# Programmer.net
KiCad netlist of a schematic drawn in EAGLE
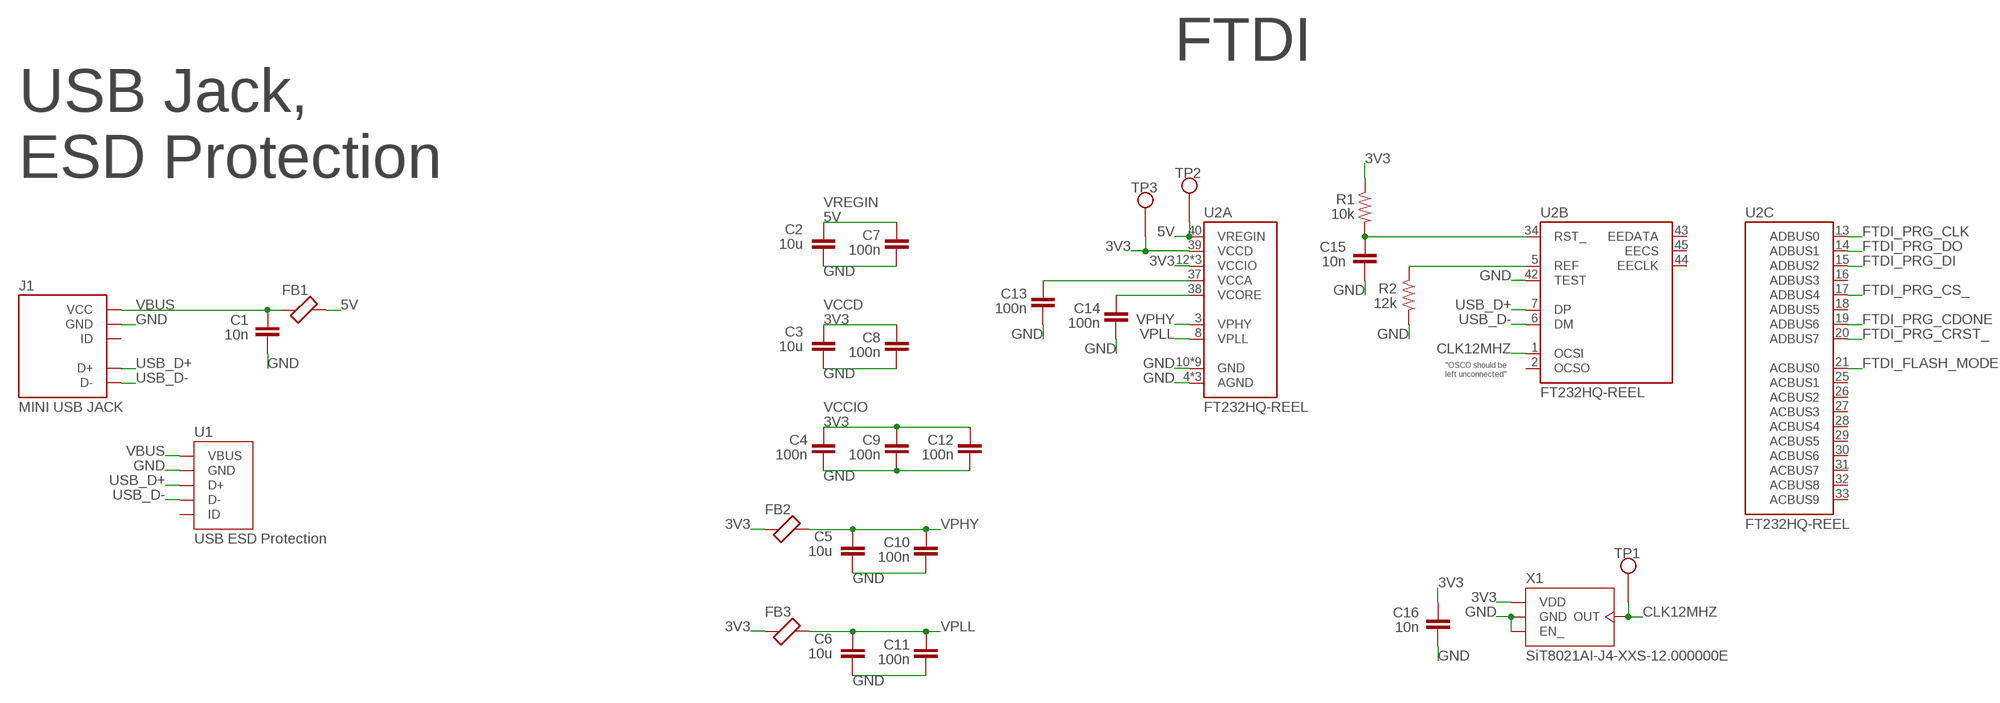
[diagram p0: schematic, sheet 1, part 1 of 2]
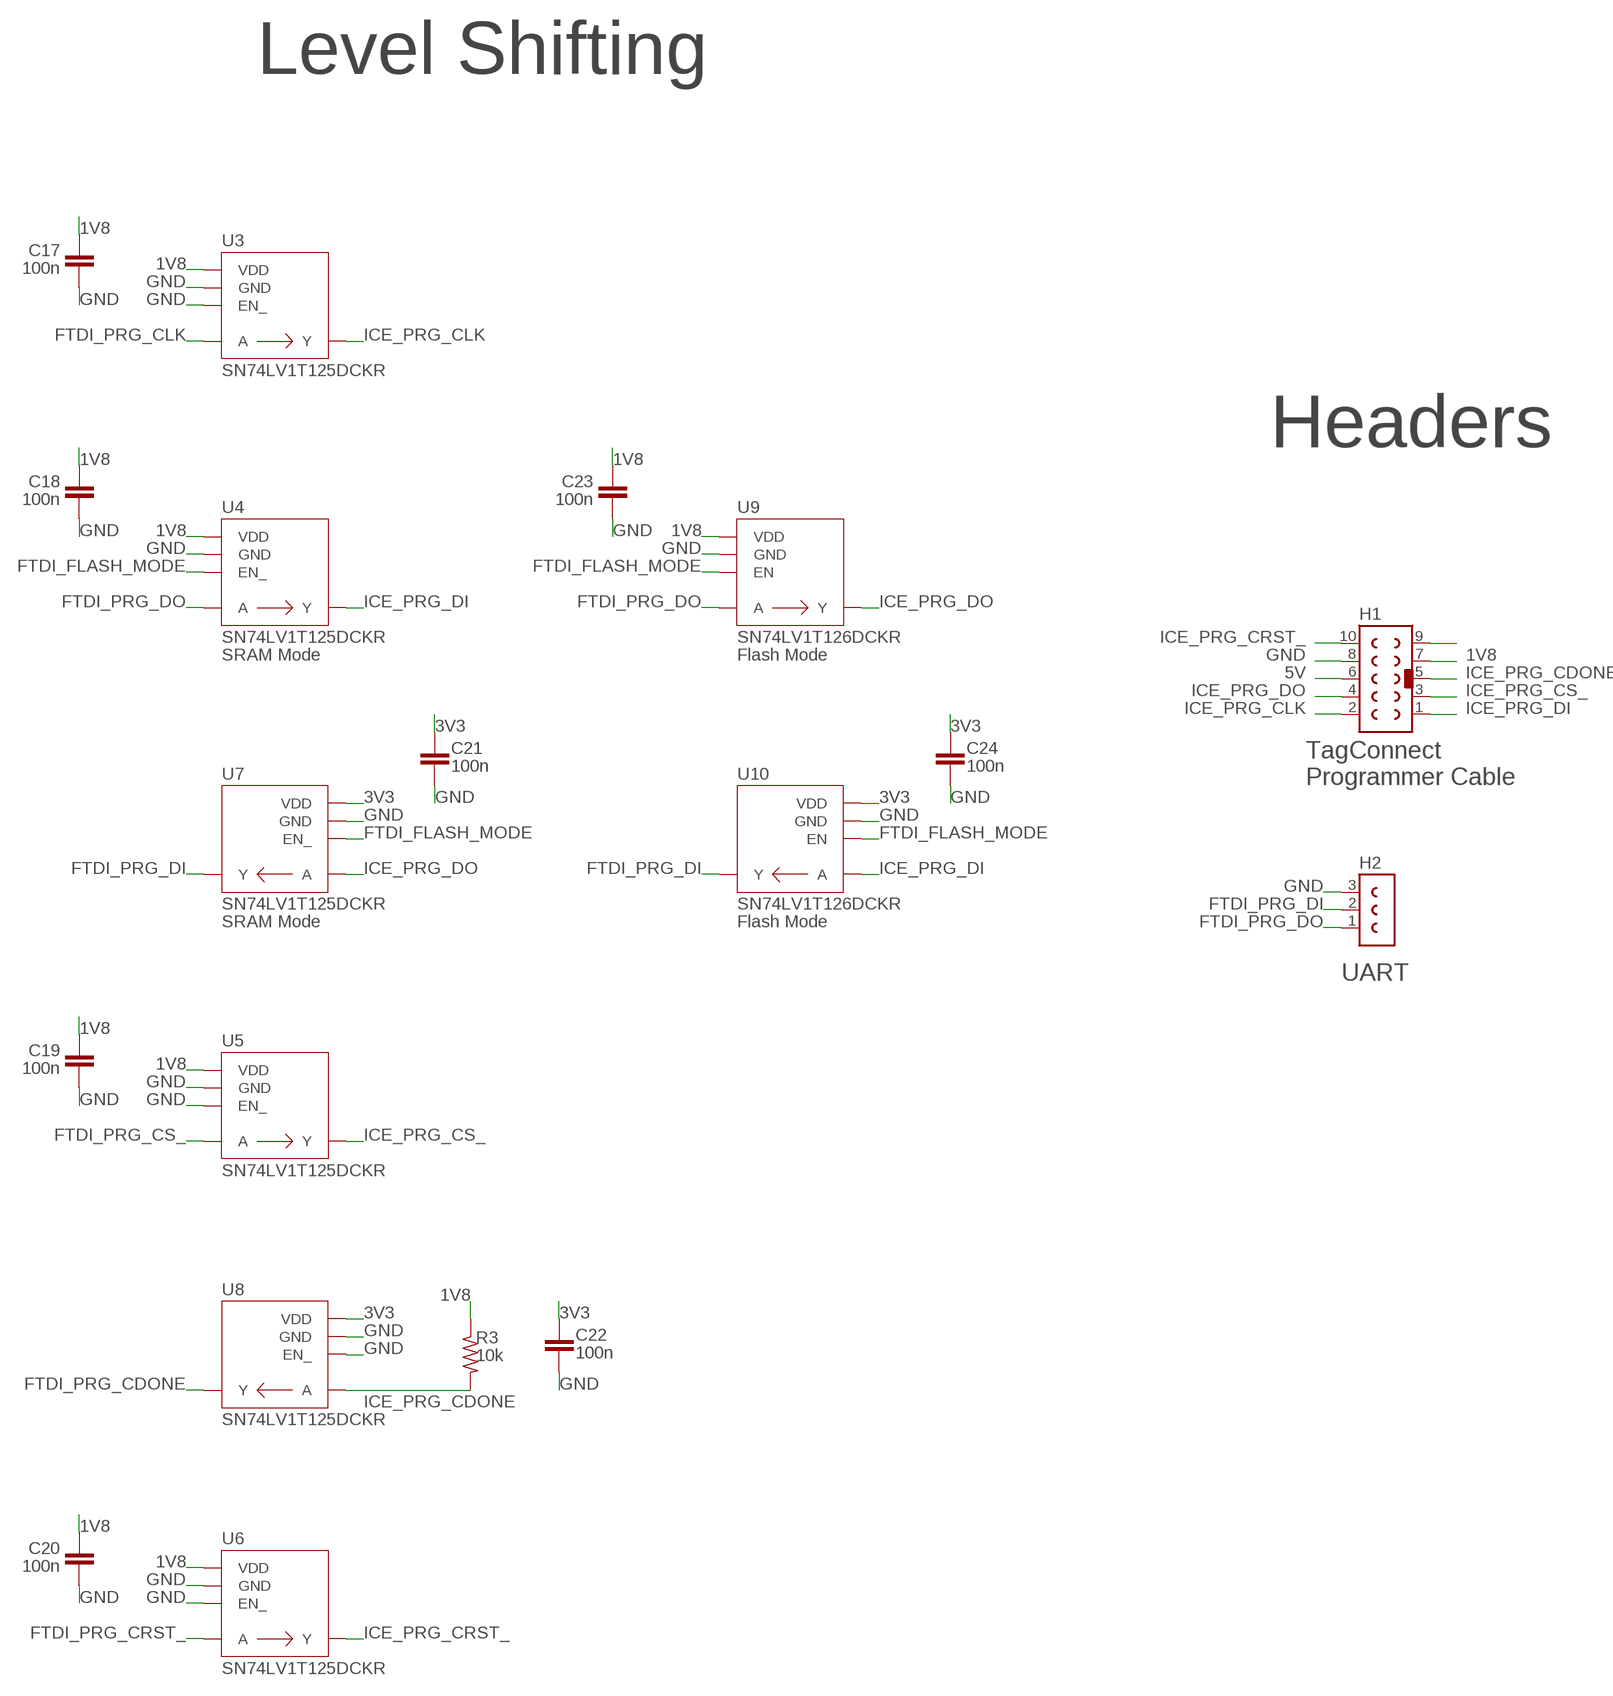
[diagram p1: schematic, sheet 1, part 2 of 2]

(export (version "E")
  (design (tool "Eeschema 10.0.6"))
  (components
    (comp (ref "C1")
      (value "10n")
      (footprint "eagle-import:0402")
      (fields (field (name "MFG") "Murata"))
      (libsource (lib "eagle-import") (part "CAPACITOR0402"))
    )
    (comp (ref "C2")
      (value "10u")
      (footprint "eagle-import:1206")
      (fields (field (name "MFG") "Murata"))
      (libsource (lib "eagle-import") (part "CAPACITOR1206"))
    )
    (comp (ref "C3")
      (value "10u")
      (footprint "eagle-import:1206")
      (fields (field (name "MFG") "Murata"))
      (libsource (lib "eagle-import") (part "CAPACITOR1206"))
    )
    (comp (ref "C4")
      (value "100n")
      (footprint "eagle-import:0402")
      (fields (field (name "MFG") "Murata"))
      (libsource (lib "eagle-import") (part "CAPACITOR0402"))
    )
    (comp (ref "C5")
      (value "10u")
      (footprint "eagle-import:1206")
      (fields (field (name "MFG") "Murata"))
      (libsource (lib "eagle-import") (part "CAPACITOR1206"))
    )
    (comp (ref "C6")
      (value "10u")
      (footprint "eagle-import:1206")
      (fields (field (name "MFG") "Murata"))
      (libsource (lib "eagle-import") (part "CAPACITOR1206"))
    )
    (comp (ref "C7")
      (value "100n")
      (footprint "eagle-import:0402")
      (fields (field (name "MFG") "Murata"))
      (libsource (lib "eagle-import") (part "CAPACITOR0402"))
    )
    (comp (ref "C8")
      (value "100n")
      (footprint "eagle-import:0402")
      (fields (field (name "MFG") "Murata"))
      (libsource (lib "eagle-import") (part "CAPACITOR0402"))
    )
    (comp (ref "C9")
      (value "100n")
      (footprint "eagle-import:0402")
      (fields (field (name "MFG") "Murata"))
      (libsource (lib "eagle-import") (part "CAPACITOR0402"))
    )
    (comp (ref "C10")
      (value "100n")
      (footprint "eagle-import:0402")
      (fields (field (name "MFG") "Murata"))
      (libsource (lib "eagle-import") (part "CAPACITOR0402"))
    )
    (comp (ref "C11")
      (value "100n")
      (footprint "eagle-import:0402")
      (fields (field (name "MFG") "Murata"))
      (libsource (lib "eagle-import") (part "CAPACITOR0402"))
    )
    (comp (ref "C12")
      (value "100n")
      (footprint "eagle-import:0402")
      (fields (field (name "MFG") "Murata"))
      (libsource (lib "eagle-import") (part "CAPACITOR0402"))
    )
    (comp (ref "C13")
      (value "100n")
      (footprint "eagle-import:0402")
      (fields (field (name "MFG") "Murata"))
      (libsource (lib "eagle-import") (part "CAPACITOR0402"))
    )
    (comp (ref "C14")
      (value "100n")
      (footprint "eagle-import:0402")
      (fields (field (name "MFG") "Murata"))
      (libsource (lib "eagle-import") (part "CAPACITOR0402"))
    )
    (comp (ref "C15")
      (value "10n")
      (footprint "eagle-import:0402")
      (fields (field (name "MFG") "Murata"))
      (libsource (lib "eagle-import") (part "CAPACITOR0402"))
    )
    (comp (ref "C16")
      (value "10n")
      (footprint "eagle-import:0402")
      (fields (field (name "MFG") "Murata"))
      (libsource (lib "eagle-import") (part "CAPACITOR0402"))
    )
    (comp (ref "C17")
      (value "100n")
      (footprint "eagle-import:0402")
      (fields (field (name "MFG") "Murata"))
      (libsource (lib "eagle-import") (part "CAPACITOR0402"))
    )
    (comp (ref "C18")
      (value "100n")
      (footprint "eagle-import:0402")
      (fields (field (name "MFG") "Murata"))
      (libsource (lib "eagle-import") (part "CAPACITOR0402"))
    )
    (comp (ref "C19")
      (value "100n")
      (footprint "eagle-import:0402")
      (fields (field (name "MFG") "Murata"))
      (libsource (lib "eagle-import") (part "CAPACITOR0402"))
    )
    (comp (ref "C20")
      (value "100n")
      (footprint "eagle-import:0402")
      (fields (field (name "MFG") "Murata"))
      (libsource (lib "eagle-import") (part "CAPACITOR0402"))
    )
    (comp (ref "C21")
      (value "100n")
      (footprint "eagle-import:0402")
      (fields (field (name "MFG") "Murata"))
      (libsource (lib "eagle-import") (part "CAPACITOR0402"))
    )
    (comp (ref "C22")
      (value "100n")
      (footprint "eagle-import:0402")
      (fields (field (name "MFG") "Murata"))
      (libsource (lib "eagle-import") (part "CAPACITOR0402"))
    )
    (comp (ref "C23")
      (value "100n")
      (footprint "eagle-import:0402")
      (fields (field (name "MFG") "Murata"))
      (libsource (lib "eagle-import") (part "CAPACITOR0402"))
    )
    (comp (ref "C24")
      (value "100n")
      (footprint "eagle-import:0402")
      (fields (field (name "MFG") "Murata"))
      (libsource (lib "eagle-import") (part "CAPACITOR0402"))
    )
    (comp (ref "FB1")
      (value "FERRITE-BEAD1206")
      (footprint "eagle-import:1206")
      (fields (field (name "MFG") "Murata"))
      (libsource (lib "eagle-import") (part "FERRITE-BEAD1206"))
    )
    (comp (ref "FB2")
      (value "FERRITE-BEAD1206")
      (footprint "eagle-import:1206")
      (fields (field (name "MFG") "Murata"))
      (libsource (lib "eagle-import") (part "FERRITE-BEAD1206"))
    )
    (comp (ref "FB3")
      (value "FERRITE-BEAD1206")
      (footprint "eagle-import:1206")
      (fields (field (name "MFG") "Murata"))
      (libsource (lib "eagle-import") (part "FERRITE-BEAD1206"))
    )
    (comp (ref "H1")
      (value "WURTH-61201021621")
      (footprint "eagle-import:WURTH-61201021621")
      (fields (field (name "MFG") "Wurth Elektronik"))
      (libsource (lib "eagle-import") (part "WURTH-61201021621"))
    )
    (comp (ref "H2")
      (value "HEADER-1X3")
      (footprint "eagle-import:HEADER-1X3")
      (fields (field (name "MFG") "Molex"))
      (libsource (lib "eagle-import") (part "HEADER-1X3"))
    )
    (comp (ref "J1")
      (value "MINI-USB-JACK")
      (footprint "eagle-import:AMPHENOLFCI-10033526-N3222MLF")
      (fields (field (name "MFG") "Amphenol FCI"))
      (libsource (lib "eagle-import") (part "MINI-USB-JACK"))
    )
    (comp (ref "R1")
      (value "10k")
      (footprint "eagle-import:0402")
      (fields (field (name "MFG") "Vishay"))
      (libsource (lib "eagle-import") (part "RESISTOR0402"))
    )
    (comp (ref "R2")
      (value "12k")
      (footprint "eagle-import:0402")
      (fields (field (name "MFG") "Vishay"))
      (libsource (lib "eagle-import") (part "RESISTOR0402"))
    )
    (comp (ref "R3")
      (value "10k")
      (footprint "eagle-import:0402")
      (fields (field (name "MFG") "Vishay"))
      (libsource (lib "eagle-import") (part "RESISTOR0402"))
    )
    (comp (ref "TP1")
      (value "TEST-POINT")
      (footprint "eagle-import:TEST-POINT")
      (libsource (lib "eagle-import") (part "TEST-POINT"))
    )
    (comp (ref "TP2")
      (value "TEST-POINT")
      (footprint "eagle-import:TEST-POINT")
      (libsource (lib "eagle-import") (part "TEST-POINT"))
    )
    (comp (ref "TP3")
      (value "TEST-POINT")
      (footprint "eagle-import:TEST-POINT")
      (libsource (lib "eagle-import") (part "TEST-POINT"))
    )
    (comp (ref "U1")
      (value "TPD4S012DRYR")
      (footprint "eagle-import:TPD4S012DRYR")
      (fields (field (name "MFG") "Texas Instruments"))
      (libsource (lib "eagle-import") (part "TPD4S012DRYR"))
    )
    (comp (ref "U2")
      (value "FT232HQ")
      (footprint "eagle-import:FT232HQ")
      (fields (field (name "MFG") "FTDI") (field (name "PN") "FT232HQ-REEL"))
      (libsource (lib "eagle-import") (part "FT232HQ"))
    )
    (comp (ref "U3")
      (value "SN74LV1T125DCKR")
      (footprint "eagle-import:SN74LV1T12XDCKR")
      (fields (field (name "PN") "SN74LV1T125DCKR") (field (name "MFG") "Texas Instruments"))
      (libsource (lib "eagle-import") (part "SN74LV1T125DCKR"))
    )
    (comp (ref "U4")
      (value "SN74LV1T125DCKR")
      (footprint "eagle-import:SN74LV1T12XDCKR")
      (fields (field (name "PN") "SN74LV1T125DCKR") (field (name "MFG") "Texas Instruments"))
      (libsource (lib "eagle-import") (part "SN74LV1T125DCKR"))
    )
    (comp (ref "U5")
      (value "SN74LV1T125DCKR")
      (footprint "eagle-import:SN74LV1T12XDCKR")
      (fields (field (name "PN") "SN74LV1T125DCKR") (field (name "MFG") "Texas Instruments"))
      (libsource (lib "eagle-import") (part "SN74LV1T125DCKR"))
    )
    (comp (ref "U6")
      (value "SN74LV1T125DCKR")
      (footprint "eagle-import:SN74LV1T12XDCKR")
      (fields (field (name "PN") "SN74LV1T125DCKR") (field (name "MFG") "Texas Instruments"))
      (libsource (lib "eagle-import") (part "SN74LV1T125DCKR"))
    )
    (comp (ref "U7")
      (value "SN74LV1T125DCKR")
      (footprint "eagle-import:SN74LV1T12XDCKR")
      (fields (field (name "PN") "SN74LV1T125DCKR") (field (name "MFG") "Texas Instruments"))
      (libsource (lib "eagle-import") (part "SN74LV1T125DCKR"))
    )
    (comp (ref "U8")
      (value "SN74LV1T125DCKR")
      (footprint "eagle-import:SN74LV1T12XDCKR")
      (fields (field (name "PN") "SN74LV1T125DCKR") (field (name "MFG") "Texas Instruments"))
      (libsource (lib "eagle-import") (part "SN74LV1T125DCKR"))
    )
    (comp (ref "U9")
      (value "SN74LV1T126DCKR")
      (footprint "eagle-import:SN74LV1T12XDCKR")
      (fields (field (name "PN") "SN74LV1T126DCKR") (field (name "MFG") "Texas Instruments"))
      (libsource (lib "eagle-import") (part "SN74LV1T126DCKR"))
    )
    (comp (ref "U10")
      (value "SN74LV1T126DCKR")
      (footprint "eagle-import:SN74LV1T12XDCKR")
      (fields (field (name "PN") "SN74LV1T126DCKR") (field (name "MFG") "Texas Instruments"))
      (libsource (lib "eagle-import") (part "SN74LV1T126DCKR"))
    )
    (comp (ref "X1")
      (value "SITIME-SIT8021")
      (footprint "eagle-import:SITIME-SIT8021")
      (fields (field (name "MFG") "SiTime") (field (name "PN") "SiT8021AI-J4-XXS-12.000000E"))
      (libsource (lib "eagle-import") (part "SITIME-SIT8021"))
    )
  )
  (nets
    (net (code "1") (name "/1V8") (class "Default")
      (node (ref "C17") (pin "1") (pinfunction "1_1") (pintype "bidirectional"))
      (node (ref "C18") (pin "1") (pinfunction "1_1") (pintype "bidirectional"))
      (node (ref "C19") (pin "1") (pinfunction "1_1") (pintype "bidirectional"))
      (node (ref "C20") (pin "1") (pinfunction "1_1") (pintype "bidirectional"))
      (node (ref "C23") (pin "1") (pinfunction "1_1") (pintype "bidirectional"))
      (node (ref "H1") (pin "7") (pinfunction "7_7") (pintype "bidirectional"))
      (node (ref "R3") (pin "1") (pinfunction "1_1") (pintype "bidirectional"))
      (node (ref "U3") (pin "5") (pinfunction "VDD_5") (pintype "bidirectional"))
      (node (ref "U4") (pin "5") (pinfunction "VDD_5") (pintype "bidirectional"))
      (node (ref "U5") (pin "5") (pinfunction "VDD_5") (pintype "bidirectional"))
      (node (ref "U6") (pin "5") (pinfunction "VDD_5") (pintype "bidirectional"))
      (node (ref "U9") (pin "5") (pinfunction "VDD_5") (pintype "bidirectional"))
    )
    (net (code "2") (name "/3V3") (class "Default")
      (node (ref "C12") (pin "1") (pinfunction "1_1") (pintype "bidirectional"))
      (node (ref "C16") (pin "1") (pinfunction "1_1") (pintype "bidirectional"))
      (node (ref "C21") (pin "1") (pinfunction "1_1") (pintype "bidirectional"))
      (node (ref "C22") (pin "1") (pinfunction "1_1") (pintype "bidirectional"))
      (node (ref "C24") (pin "1") (pinfunction "1_1") (pintype "bidirectional"))
      (node (ref "C3") (pin "1") (pinfunction "1_1") (pintype "bidirectional"))
      (node (ref "C4") (pin "1") (pinfunction "1_1") (pintype "bidirectional"))
      (node (ref "C8") (pin "1") (pinfunction "1_1") (pintype "bidirectional"))
      (node (ref "C9") (pin "1") (pinfunction "1_1") (pintype "bidirectional"))
      (node (ref "FB2") (pin "1") (pinfunction "P$1_1") (pintype "bidirectional"))
      (node (ref "FB3") (pin "1") (pinfunction "P$1_1") (pintype "bidirectional"))
      (node (ref "R1") (pin "1") (pinfunction "1_1") (pintype "bidirectional"))
      (node (ref "TP3") (pin "X") (pinfunction "X_X") (pintype "bidirectional"))
      (node (ref "U10") (pin "5") (pinfunction "VDD_5") (pintype "bidirectional"))
      (node (ref "U2") (pin "12") (pinfunction "VCCIO_12") (pintype "bidirectional"))
      (node (ref "U2") (pin "24") (pinfunction "VCCIO_24") (pintype "bidirectional"))
      (node (ref "U2") (pin "39") (pinfunction "VCCD_39") (pintype "bidirectional"))
      (node (ref "U2") (pin "46") (pinfunction "VCCIO_46") (pintype "bidirectional"))
      (node (ref "U7") (pin "5") (pinfunction "VDD_5") (pintype "bidirectional"))
      (node (ref "U8") (pin "5") (pinfunction "VDD_5") (pintype "bidirectional"))
      (node (ref "X1") (pin "3") (pinfunction "VDD_3") (pintype "bidirectional"))
    )
    (net (code "3") (name "/5V") (class "Default")
      (node (ref "C2") (pin "1") (pinfunction "1_1") (pintype "bidirectional"))
      (node (ref "C7") (pin "1") (pinfunction "1_1") (pintype "bidirectional"))
      (node (ref "FB1") (pin "2") (pinfunction "P$2_2") (pintype "bidirectional"))
      (node (ref "H1") (pin "6") (pinfunction "6_6") (pintype "bidirectional"))
      (node (ref "TP2") (pin "X") (pinfunction "X_X") (pintype "bidirectional"))
      (node (ref "U2") (pin "40") (pinfunction "VREGIN_40") (pintype "bidirectional"))
    )
    (net (code "4") (name "/CLK12MHZ") (class "Default")
      (node (ref "TP1") (pin "X") (pinfunction "X_X") (pintype "bidirectional"))
      (node (ref "U2") (pin "1") (pinfunction "OCSI_1") (pintype "bidirectional"))
      (node (ref "X1") (pin "2") (pinfunction "OUT_2") (pintype "bidirectional"))
    )
    (net (code "5") (name "/FTDI_FLASH_MODE") (class "Default")
      (node (ref "U10") (pin "1") (pinfunction "EN_1") (pintype "input"))
      (node (ref "U2") (pin "21") (pinfunction "ACBUS0_21") (pintype "bidirectional"))
      (node (ref "U4") (pin "1") (pinfunction "EN__1") (pintype "input"))
      (node (ref "U7") (pin "1") (pinfunction "EN__1") (pintype "input"))
      (node (ref "U9") (pin "1") (pinfunction "EN_1") (pintype "input"))
    )
    (net (code "6") (name "/FTDI_PRG_CDONE") (class "Default")
      (node (ref "U2") (pin "19") (pinfunction "ADBUS6_19") (pintype "bidirectional"))
      (node (ref "U8") (pin "4") (pinfunction "Y_4") (pintype "input"))
    )
    (net (code "7") (name "/FTDI_PRG_CLK") (class "Default")
      (node (ref "U2") (pin "13") (pinfunction "ADBUS0_13") (pintype "bidirectional"))
      (node (ref "U3") (pin "2") (pinfunction "A_2") (pintype "input"))
    )
    (net (code "8") (name "/FTDI_PRG_CRST_") (class "Default")
      (node (ref "U2") (pin "20") (pinfunction "ADBUS7_20") (pintype "bidirectional"))
      (node (ref "U6") (pin "2") (pinfunction "A_2") (pintype "input"))
    )
    (net (code "9") (name "/FTDI_PRG_CS_") (class "Default")
      (node (ref "U2") (pin "17") (pinfunction "ADBUS4_17") (pintype "bidirectional"))
      (node (ref "U5") (pin "2") (pinfunction "A_2") (pintype "input"))
    )
    (net (code "10") (name "/FTDI_PRG_DI") (class "Default")
      (node (ref "H2") (pin "2") (pinfunction "2_2") (pintype "bidirectional"))
      (node (ref "U10") (pin "4") (pinfunction "Y_4") (pintype "input"))
      (node (ref "U2") (pin "15") (pinfunction "ADBUS2_15") (pintype "bidirectional"))
      (node (ref "U7") (pin "4") (pinfunction "Y_4") (pintype "input"))
    )
    (net (code "11") (name "/FTDI_PRG_DO") (class "Default")
      (node (ref "H2") (pin "1") (pinfunction "1_1") (pintype "bidirectional"))
      (node (ref "U2") (pin "14") (pinfunction "ADBUS1_14") (pintype "bidirectional"))
      (node (ref "U4") (pin "2") (pinfunction "A_2") (pintype "input"))
      (node (ref "U9") (pin "2") (pinfunction "A_2") (pintype "input"))
    )
    (net (code "12") (name "/GND") (class "Default")
      (node (ref "C1") (pin "2") (pinfunction "2_2") (pintype "bidirectional"))
      (node (ref "C10") (pin "2") (pinfunction "2_2") (pintype "bidirectional"))
      (node (ref "C11") (pin "2") (pinfunction "2_2") (pintype "bidirectional"))
      (node (ref "C12") (pin "2") (pinfunction "2_2") (pintype "bidirectional"))
      (node (ref "C13") (pin "2") (pinfunction "2_2") (pintype "bidirectional"))
      (node (ref "C14") (pin "2") (pinfunction "2_2") (pintype "bidirectional"))
      (node (ref "C15") (pin "2") (pinfunction "2_2") (pintype "bidirectional"))
      (node (ref "C16") (pin "2") (pinfunction "2_2") (pintype "bidirectional"))
      (node (ref "C17") (pin "2") (pinfunction "2_2") (pintype "bidirectional"))
      (node (ref "C18") (pin "2") (pinfunction "2_2") (pintype "bidirectional"))
      (node (ref "C19") (pin "2") (pinfunction "2_2") (pintype "bidirectional"))
      (node (ref "C2") (pin "2") (pinfunction "2_2") (pintype "bidirectional"))
      (node (ref "C20") (pin "2") (pinfunction "2_2") (pintype "bidirectional"))
      (node (ref "C21") (pin "2") (pinfunction "2_2") (pintype "bidirectional"))
      (node (ref "C22") (pin "2") (pinfunction "2_2") (pintype "bidirectional"))
      (node (ref "C23") (pin "2") (pinfunction "2_2") (pintype "bidirectional"))
      (node (ref "C24") (pin "2") (pinfunction "2_2") (pintype "bidirectional"))
      (node (ref "C3") (pin "2") (pinfunction "2_2") (pintype "bidirectional"))
      (node (ref "C4") (pin "2") (pinfunction "2_2") (pintype "bidirectional"))
      (node (ref "C5") (pin "2") (pinfunction "2_2") (pintype "bidirectional"))
      (node (ref "C6") (pin "2") (pinfunction "2_2") (pintype "bidirectional"))
      (node (ref "C7") (pin "2") (pinfunction "2_2") (pintype "bidirectional"))
      (node (ref "C8") (pin "2") (pinfunction "2_2") (pintype "bidirectional"))
      (node (ref "C9") (pin "2") (pinfunction "2_2") (pintype "bidirectional"))
      (node (ref "H1") (pin "8") (pinfunction "8_8") (pintype "bidirectional"))
      (node (ref "H2") (pin "3") (pinfunction "3_3") (pintype "bidirectional"))
      (node (ref "J1") (pin "GND") (pinfunction "GND_GND") (pintype "bidirectional"))
      (node (ref "J1") (pin "GND2") (pinfunction "GND_GND2") (pintype "bidirectional"))
      (node (ref "J1") (pin "GND3") (pinfunction "GND_GND3") (pintype "bidirectional"))
      (node (ref "J1") (pin "GND4") (pinfunction "GND_GND4") (pintype "bidirectional"))
      (node (ref "J1") (pin "GND5") (pinfunction "GND_GND5") (pintype "bidirectional"))
      (node (ref "R2") (pin "2") (pinfunction "2_2") (pintype "bidirectional"))
      (node (ref "U1") (pin "4") (pinfunction "GND_4") (pintype "bidirectional"))
      (node (ref "U10") (pin "3") (pinfunction "GND_3") (pintype "bidirectional"))
      (node (ref "U2") (pin "10") (pinfunction "GND_10") (pintype "bidirectional"))
      (node (ref "U2") (pin "11") (pinfunction "GND_11") (pintype "bidirectional"))
      (node (ref "U2") (pin "22") (pinfunction "GND_22") (pintype "bidirectional"))
      (node (ref "U2") (pin "23") (pinfunction "GND_23") (pintype "bidirectional"))
      (node (ref "U2") (pin "35") (pinfunction "GND_35") (pintype "bidirectional"))
      (node (ref "U2") (pin "36") (pinfunction "GND_36") (pintype "bidirectional"))
      (node (ref "U2") (pin "4") (pinfunction "AGND_4") (pintype "bidirectional"))
      (node (ref "U2") (pin "41") (pinfunction "AGND_41") (pintype "bidirectional"))
      (node (ref "U2") (pin "42") (pinfunction "TEST_42") (pintype "bidirectional"))
      (node (ref "U2") (pin "47") (pinfunction "GND_47") (pintype "bidirectional"))
      (node (ref "U2") (pin "48") (pinfunction "GND_48") (pintype "bidirectional"))
      (node (ref "U2") (pin "49") (pinfunction "GND_49") (pintype "bidirectional"))
      (node (ref "U2") (pin "9") (pinfunction "AGND_9") (pintype "bidirectional"))
      (node (ref "U3") (pin "1") (pinfunction "EN__1") (pintype "input"))
      (node (ref "U3") (pin "3") (pinfunction "GND_3") (pintype "bidirectional"))
      (node (ref "U4") (pin "3") (pinfunction "GND_3") (pintype "bidirectional"))
      (node (ref "U5") (pin "1") (pinfunction "EN__1") (pintype "input"))
      (node (ref "U5") (pin "3") (pinfunction "GND_3") (pintype "bidirectional"))
      (node (ref "U6") (pin "1") (pinfunction "EN__1") (pintype "input"))
      (node (ref "U6") (pin "3") (pinfunction "GND_3") (pintype "bidirectional"))
      (node (ref "U7") (pin "3") (pinfunction "GND_3") (pintype "bidirectional"))
      (node (ref "U8") (pin "1") (pinfunction "EN__1") (pintype "input"))
      (node (ref "U8") (pin "3") (pinfunction "GND_3") (pintype "bidirectional"))
      (node (ref "U9") (pin "3") (pinfunction "GND_3") (pintype "bidirectional"))
      (node (ref "X1") (pin "1") (pinfunction "EN__1") (pintype "input"))
      (node (ref "X1") (pin "4") (pinfunction "GND_4") (pintype "bidirectional"))
    )
    (net (code "13") (name "/ICE_PRG_CDONE") (class "Default")
      (node (ref "H1") (pin "5") (pinfunction "5_5") (pintype "bidirectional"))
      (node (ref "R3") (pin "2") (pinfunction "2_2") (pintype "bidirectional"))
      (node (ref "U8") (pin "2") (pinfunction "A_2") (pintype "input"))
    )
    (net (code "14") (name "/ICE_PRG_CLK") (class "Default")
      (node (ref "H1") (pin "2") (pinfunction "2_2") (pintype "bidirectional"))
      (node (ref "U3") (pin "4") (pinfunction "Y_4") (pintype "input"))
    )
    (net (code "15") (name "/ICE_PRG_CRST_") (class "Default")
      (node (ref "H1") (pin "10") (pinfunction "10_10") (pintype "bidirectional"))
      (node (ref "U6") (pin "4") (pinfunction "Y_4") (pintype "input"))
    )
    (net (code "16") (name "/ICE_PRG_CS_") (class "Default")
      (node (ref "H1") (pin "3") (pinfunction "3_3") (pintype "bidirectional"))
      (node (ref "U5") (pin "4") (pinfunction "Y_4") (pintype "input"))
    )
    (net (code "17") (name "/ICE_PRG_DI") (class "Default")
      (node (ref "H1") (pin "1") (pinfunction "1_1") (pintype "bidirectional"))
      (node (ref "U10") (pin "2") (pinfunction "A_2") (pintype "input"))
      (node (ref "U4") (pin "4") (pinfunction "Y_4") (pintype "input"))
    )
    (net (code "18") (name "/ICE_PRG_DO") (class "Default")
      (node (ref "H1") (pin "4") (pinfunction "4_4") (pintype "bidirectional"))
      (node (ref "U7") (pin "2") (pinfunction "A_2") (pintype "input"))
      (node (ref "U9") (pin "4") (pinfunction "Y_4") (pintype "input"))
    )
    (net (code "19") (name "/USB_D+") (class "Default")
      (node (ref "J1") (pin "D+") (pinfunction "D+_D+") (pintype "bidirectional"))
      (node (ref "U1") (pin "1") (pinfunction "D+_1") (pintype "bidirectional"))
      (node (ref "U2") (pin "7") (pinfunction "DP_7") (pintype "bidirectional"))
    )
    (net (code "20") (name "/USB_D-") (class "Default")
      (node (ref "J1") (pin "D-") (pinfunction "D-_D-") (pintype "bidirectional"))
      (node (ref "U1") (pin "2") (pinfunction "D-_2") (pintype "bidirectional"))
      (node (ref "U2") (pin "6") (pinfunction "DM_6") (pintype "bidirectional"))
    )
    (net (code "21") (name "/VBUS") (class "Default")
      (node (ref "C1") (pin "1") (pinfunction "1_1") (pintype "bidirectional"))
      (node (ref "FB1") (pin "1") (pinfunction "P$1_1") (pintype "bidirectional"))
      (node (ref "J1") (pin "VCC") (pinfunction "VCC_VCC") (pintype "bidirectional"))
      (node (ref "U1") (pin "6") (pinfunction "VBUS_6") (pintype "bidirectional"))
    )
    (net (code "22") (name "/VPHY") (class "Default")
      (node (ref "C10") (pin "1") (pinfunction "1_1") (pintype "bidirectional"))
      (node (ref "C5") (pin "1") (pinfunction "1_1") (pintype "bidirectional"))
      (node (ref "FB2") (pin "2") (pinfunction "P$2_2") (pintype "bidirectional"))
      (node (ref "U2") (pin "3") (pinfunction "VPHY_3") (pintype "bidirectional"))
    )
    (net (code "23") (name "/VPLL") (class "Default")
      (node (ref "C11") (pin "1") (pinfunction "1_1") (pintype "bidirectional"))
      (node (ref "C6") (pin "1") (pinfunction "1_1") (pintype "bidirectional"))
      (node (ref "FB3") (pin "2") (pinfunction "P$2_2") (pintype "bidirectional"))
      (node (ref "U2") (pin "8") (pinfunction "VPLL_8") (pintype "bidirectional"))
    )
    (net (code "24") (name "Net-(U2A-VCCA)") (class "Default")
      (node (ref "C13") (pin "1") (pinfunction "1_1") (pintype "bidirectional"))
      (node (ref "U2") (pin "37") (pinfunction "VCCA_37") (pintype "bidirectional"))
    )
    (net (code "25") (name "Net-(U2A-VCORE)") (class "Default")
      (node (ref "C14") (pin "1") (pinfunction "1_1") (pintype "bidirectional"))
      (node (ref "U2") (pin "38") (pinfunction "VCORE_38") (pintype "bidirectional"))
    )
    (net (code "26") (name "Net-(U2B-REF)") (class "Default")
      (node (ref "R2") (pin "1") (pinfunction "1_1") (pintype "bidirectional"))
      (node (ref "U2") (pin "5") (pinfunction "REF_5") (pintype "bidirectional"))
    )
    (net (code "27") (name "Net-(U2B-RST_)") (class "Default")
      (node (ref "C15") (pin "1") (pinfunction "1_1") (pintype "bidirectional"))
      (node (ref "R1") (pin "2") (pinfunction "2_2") (pintype "bidirectional"))
      (node (ref "U2") (pin "34") (pinfunction "RST__34") (pintype "bidirectional"))
    )
    (net (code "28") (name "unconnected-(H1-Pad9)") (class "Default")
      (node (ref "H1") (pin "9") (pinfunction "9_9") (pintype "bidirectional"))
    )
    (net (code "29") (name "unconnected-(J1-PadID)") (class "Default")
      (node (ref "J1") (pin "ID") (pinfunction "ID_ID") (pintype "bidirectional"))
    )
    (net (code "30") (name "unconnected-(U1-ID-Pad3)") (class "Default")
      (node (ref "U1") (pin "3") (pinfunction "ID_3") (pintype "bidirectional"))
    )
    (net (code "31") (name "unconnected-(U2B-EECLK-Pad44)") (class "Default")
      (node (ref "U2") (pin "44") (pinfunction "EECLK_44") (pintype "bidirectional"))
    )
    (net (code "32") (name "unconnected-(U2B-EECS-Pad45)") (class "Default")
      (node (ref "U2") (pin "45") (pinfunction "EECS_45") (pintype "bidirectional"))
    )
    (net (code "33") (name "unconnected-(U2B-EEDATA-Pad43)") (class "Default")
      (node (ref "U2") (pin "43") (pinfunction "EEDATA_43") (pintype "bidirectional"))
    )
    (net (code "34") (name "unconnected-(U2B-OCSO-Pad2)") (class "Default")
      (node (ref "U2") (pin "2") (pinfunction "OCSO_2") (pintype "bidirectional"))
    )
    (net (code "35") (name "unconnected-(U2C-ACBUS1-Pad25)") (class "Default")
      (node (ref "U2") (pin "25") (pinfunction "ACBUS1_25") (pintype "bidirectional"))
    )
    (net (code "36") (name "unconnected-(U2C-ACBUS2-Pad26)") (class "Default")
      (node (ref "U2") (pin "26") (pinfunction "ACBUS2_26") (pintype "bidirectional"))
    )
    (net (code "37") (name "unconnected-(U2C-ACBUS3-Pad27)") (class "Default")
      (node (ref "U2") (pin "27") (pinfunction "ACBUS3_27") (pintype "bidirectional"))
    )
    (net (code "38") (name "unconnected-(U2C-ACBUS4-Pad28)") (class "Default")
      (node (ref "U2") (pin "28") (pinfunction "ACBUS4_28") (pintype "bidirectional"))
    )
    (net (code "39") (name "unconnected-(U2C-ACBUS5-Pad29)") (class "Default")
      (node (ref "U2") (pin "29") (pinfunction "ACBUS5_29") (pintype "bidirectional"))
    )
    (net (code "40") (name "unconnected-(U2C-ACBUS6-Pad30)") (class "Default")
      (node (ref "U2") (pin "30") (pinfunction "ACBUS6_30") (pintype "bidirectional"))
    )
    (net (code "41") (name "unconnected-(U2C-ACBUS7-Pad31)") (class "Default")
      (node (ref "U2") (pin "31") (pinfunction "ACBUS7_31") (pintype "bidirectional"))
    )
    (net (code "42") (name "unconnected-(U2C-ACBUS8-Pad32)") (class "Default")
      (node (ref "U2") (pin "32") (pinfunction "ACBUS8_32") (pintype "bidirectional"))
    )
    (net (code "43") (name "unconnected-(U2C-ACBUS9-Pad33)") (class "Default")
      (node (ref "U2") (pin "33") (pinfunction "ACBUS9_33") (pintype "bidirectional"))
    )
    (net (code "44") (name "unconnected-(U2C-ADBUS3-Pad16)") (class "Default")
      (node (ref "U2") (pin "16") (pinfunction "ADBUS3_16") (pintype "bidirectional"))
    )
    (net (code "45") (name "unconnected-(U2C-ADBUS5-Pad18)") (class "Default")
      (node (ref "U2") (pin "18") (pinfunction "ADBUS5_18") (pintype "bidirectional"))
    )
  )
)
